# 5_line.net
KiCad netlist of a schematic drawn in Altium Designer
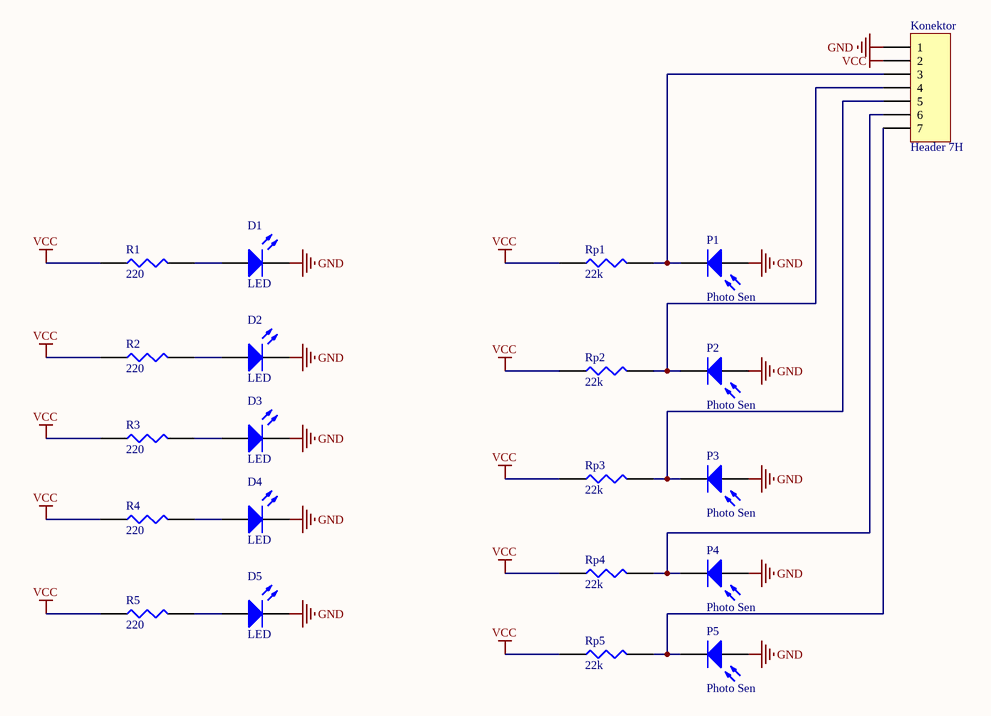
[diagram p0: 5 line.SchDoc]

(export (version "E")
  (design (tool "Eeschema 10.0.6"))
  (components
    (comp (ref "D1")
      (value "LED")
      (footprint "My_LED3MM")
      (description "Typical INFRARED GaAs LED")
      (fields (field (name "PUBLISHER") "Altium Limited"))
      (libsource (lib "Mylib") (part "LED"))
    )
    (comp (ref "D2")
      (value "LED")
      (footprint "My_LED3MM")
      (description "Typical INFRARED GaAs LED")
      (fields (field (name "PUBLISHER") "Altium Limited"))
      (libsource (lib "Mylib") (part "LED"))
    )
    (comp (ref "D3")
      (value "LED")
      (footprint "My_LED3MM")
      (description "Typical INFRARED GaAs LED")
      (fields (field (name "PUBLISHER") "Altium Limited"))
      (libsource (lib "Mylib") (part "LED"))
    )
    (comp (ref "D4")
      (value "LED")
      (footprint "My_LED3MM")
      (description "Typical INFRARED GaAs LED")
      (fields (field (name "PUBLISHER") "Altium Limited"))
      (libsource (lib "Mylib") (part "LED"))
    )
    (comp (ref "D5")
      (value "LED")
      (footprint "My_LED3MM")
      (description "Typical INFRARED GaAs LED")
      (fields (field (name "PUBLISHER") "Altium Limited"))
      (libsource (lib "Mylib") (part "LED"))
    )
    (comp (ref "Konektor")
      (value "Header 7H")
      (footprint "HDR1X7H")
      (description "Header, 7-Pin, Right Angle")
      (fields (field (name "PUBLISHER") "Altium Limited"))
      (libsource (lib "Miscellaneous Connectors") (part "Header 7H"))
    )
    (comp (ref "P1")
      (value "Photo Sen")
      (footprint "PIN2")
      (description "Photosensitive Diode")
      (fields (field (name "PUBLISHER") "Altium Limited"))
      (libsource (lib "Miscellaneous Devices") (part "Photo Sen"))
    )
    (comp (ref "P2")
      (value "Photo Sen")
      (footprint "PIN2")
      (description "Photosensitive Diode")
      (fields (field (name "PUBLISHER") "Altium Limited"))
      (libsource (lib "Miscellaneous Devices") (part "Photo Sen"))
    )
    (comp (ref "P3")
      (value "Photo Sen")
      (footprint "PIN2")
      (description "Photosensitive Diode")
      (fields (field (name "PUBLISHER") "Altium Limited"))
      (libsource (lib "Miscellaneous Devices") (part "Photo Sen"))
    )
    (comp (ref "P4")
      (value "Photo Sen")
      (footprint "PIN2")
      (description "Photosensitive Diode")
      (fields (field (name "PUBLISHER") "Altium Limited"))
      (libsource (lib "Miscellaneous Devices") (part "Photo Sen"))
    )
    (comp (ref "P5")
      (value "Photo Sen")
      (footprint "PIN2")
      (description "Photosensitive Diode")
      (fields (field (name "PUBLISHER") "Altium Limited"))
      (libsource (lib "Miscellaneous Devices") (part "Photo Sen"))
    )
    (comp (ref "R1")
      (value "220")
      (footprint "My_axial-0.4")
      (description "resistor 1/4 wat")
      (fields (field (name "Comment") "1k"))
      (libsource (lib "Mylib") (part "Res"))
    )
    (comp (ref "R2")
      (value "220")
      (footprint "My_axial-0.4")
      (description "resistor 1/4 wat")
      (fields (field (name "Comment") "1k"))
      (libsource (lib "Mylib") (part "Res"))
    )
    (comp (ref "R3")
      (value "220")
      (footprint "My_axial-0.4")
      (description "resistor 1/4 wat")
      (fields (field (name "Comment") "1k"))
      (libsource (lib "Mylib") (part "Res"))
    )
    (comp (ref "R4")
      (value "220")
      (footprint "My_axial-0.4")
      (description "resistor 1/4 wat")
      (fields (field (name "Comment") "1k"))
      (libsource (lib "Mylib") (part "Res"))
    )
    (comp (ref "R5")
      (value "220")
      (footprint "My_axial-0.4")
      (description "resistor 1/4 wat")
      (fields (field (name "Comment") "1k"))
      (libsource (lib "Mylib") (part "Res"))
    )
    (comp (ref "Rp1")
      (value "22k")
      (footprint "My_axial-0.4")
      (description "resistor 1/4 wat")
      (fields (field (name "Comment") "1k"))
      (libsource (lib "Mylib") (part "Res"))
    )
    (comp (ref "Rp2")
      (value "22k")
      (footprint "My_axial-0.4")
      (description "resistor 1/4 wat")
      (fields (field (name "Comment") "1k"))
      (libsource (lib "Mylib") (part "Res"))
    )
    (comp (ref "Rp3")
      (value "22k")
      (footprint "My_axial-0.4")
      (description "resistor 1/4 wat")
      (fields (field (name "Comment") "1k"))
      (libsource (lib "Mylib") (part "Res"))
    )
    (comp (ref "Rp4")
      (value "22k")
      (footprint "My_axial-0.4")
      (description "resistor 1/4 wat")
      (fields (field (name "Comment") "1k"))
      (libsource (lib "Mylib") (part "Res"))
    )
    (comp (ref "Rp5")
      (value "22k")
      (footprint "My_axial-0.4")
      (description "resistor 1/4 wat")
      (fields (field (name "Comment") "1k"))
      (libsource (lib "Mylib") (part "Res"))
    )
  )
  (nets
    (net (code "1") (name "GND") (class "Default")
      (node (ref "D1") (pin "K") (pinfunction "K_K") (pintype "passive"))
      (node (ref "D2") (pin "K") (pinfunction "K_K") (pintype "passive"))
      (node (ref "D3") (pin "K") (pinfunction "K_K") (pintype "passive"))
      (node (ref "D4") (pin "K") (pinfunction "K_K") (pintype "passive"))
      (node (ref "D5") (pin "K") (pinfunction "K_K") (pintype "passive"))
      (node (ref "Konektor") (pin "1") (pinfunction "1_1") (pintype "passive"))
      (node (ref "P1") (pin "1") (pinfunction "A_1") (pintype "passive"))
      (node (ref "P2") (pin "1") (pinfunction "A_1") (pintype "passive"))
      (node (ref "P3") (pin "1") (pinfunction "A_1") (pintype "passive"))
      (node (ref "P4") (pin "1") (pinfunction "A_1") (pintype "passive"))
      (node (ref "P5") (pin "1") (pinfunction "A_1") (pintype "passive"))
    )
    (net (code "2") (name "Net-(D1-PadA)") (class "Default")
      (node (ref "D1") (pin "A") (pinfunction "A_A") (pintype "passive"))
      (node (ref "R1") (pin "2") (pinfunction "2_2") (pintype "passive"))
    )
    (net (code "3") (name "Net-(D2-PadA)") (class "Default")
      (node (ref "D2") (pin "A") (pinfunction "A_A") (pintype "passive"))
      (node (ref "R2") (pin "2") (pinfunction "2_2") (pintype "passive"))
    )
    (net (code "4") (name "Net-(D3-PadA)") (class "Default")
      (node (ref "D3") (pin "A") (pinfunction "A_A") (pintype "passive"))
      (node (ref "R3") (pin "2") (pinfunction "2_2") (pintype "passive"))
    )
    (net (code "5") (name "Net-(D4-PadA)") (class "Default")
      (node (ref "D4") (pin "A") (pinfunction "A_A") (pintype "passive"))
      (node (ref "R4") (pin "2") (pinfunction "2_2") (pintype "passive"))
    )
    (net (code "6") (name "Net-(D5-PadA)") (class "Default")
      (node (ref "D5") (pin "A") (pinfunction "A_A") (pintype "passive"))
      (node (ref "R5") (pin "2") (pinfunction "2_2") (pintype "passive"))
    )
    (net (code "7") (name "Net-(P1-K)") (class "Default")
      (node (ref "Konektor") (pin "3") (pinfunction "3_3") (pintype "passive"))
      (node (ref "P1") (pin "2") (pinfunction "K_2") (pintype "passive"))
      (node (ref "Rp1") (pin "2") (pinfunction "2_2") (pintype "passive"))
    )
    (net (code "8") (name "Net-(P2-K)") (class "Default")
      (node (ref "Konektor") (pin "4") (pinfunction "4_4") (pintype "passive"))
      (node (ref "P2") (pin "2") (pinfunction "K_2") (pintype "passive"))
      (node (ref "Rp2") (pin "2") (pinfunction "2_2") (pintype "passive"))
    )
    (net (code "9") (name "Net-(P3-K)") (class "Default")
      (node (ref "Konektor") (pin "5") (pinfunction "5_5") (pintype "passive"))
      (node (ref "P3") (pin "2") (pinfunction "K_2") (pintype "passive"))
      (node (ref "Rp3") (pin "2") (pinfunction "2_2") (pintype "passive"))
    )
    (net (code "10") (name "Net-(P4-K)") (class "Default")
      (node (ref "Konektor") (pin "6") (pinfunction "6_6") (pintype "passive"))
      (node (ref "P4") (pin "2") (pinfunction "K_2") (pintype "passive"))
      (node (ref "Rp4") (pin "2") (pinfunction "2_2") (pintype "passive"))
    )
    (net (code "11") (name "Net-(P5-K)") (class "Default")
      (node (ref "Konektor") (pin "7") (pinfunction "7_7") (pintype "passive"))
      (node (ref "P5") (pin "2") (pinfunction "K_2") (pintype "passive"))
      (node (ref "Rp5") (pin "2") (pinfunction "2_2") (pintype "passive"))
    )
    (net (code "12") (name "VCC") (class "Default")
      (node (ref "Konektor") (pin "2") (pinfunction "2_2") (pintype "passive"))
      (node (ref "R1") (pin "1") (pinfunction "1_1") (pintype "passive"))
      (node (ref "R2") (pin "1") (pinfunction "1_1") (pintype "passive"))
      (node (ref "R3") (pin "1") (pinfunction "1_1") (pintype "passive"))
      (node (ref "R4") (pin "1") (pinfunction "1_1") (pintype "passive"))
      (node (ref "R5") (pin "1") (pinfunction "1_1") (pintype "passive"))
      (node (ref "Rp1") (pin "1") (pinfunction "1_1") (pintype "passive"))
      (node (ref "Rp2") (pin "1") (pinfunction "1_1") (pintype "passive"))
      (node (ref "Rp3") (pin "1") (pinfunction "1_1") (pintype "passive"))
      (node (ref "Rp4") (pin "1") (pinfunction "1_1") (pintype "passive"))
      (node (ref "Rp5") (pin "1") (pinfunction "1_1") (pintype "passive"))
    )
  )
)
